# USB.net
KiCad netlist of a schematic drawn in Altium Designer
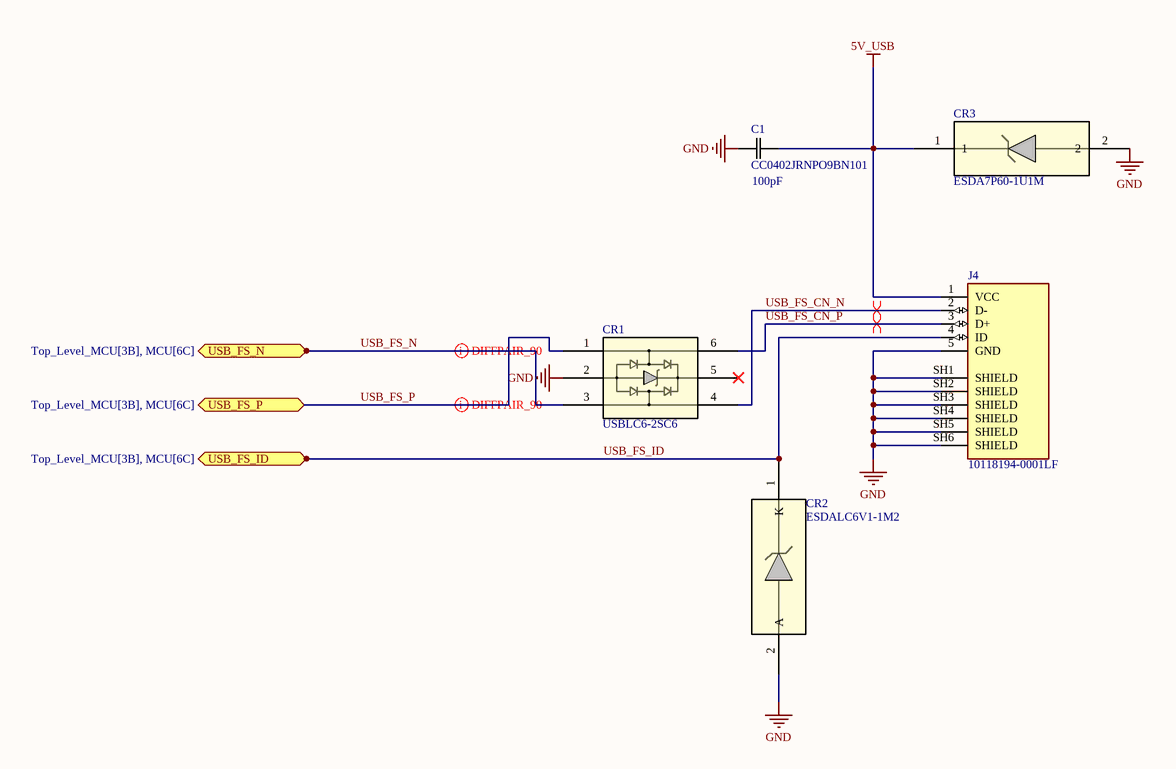
[diagram p0: USB.SchDoc]

(export (version "E")
  (design (tool "Eeschema 10.0.6"))
  (components
    (comp (ref "C1")
      (value "CC0402JRNPO9BN101")
      (footprint "CAP_CC0402_YAG")
      (description "CAPACITOR; SMT (0402); CERAMIC CHIP; 100PF; 50V; TOL=5%; TG=-55 DEGC TO +125 DEGC; TC=C0G")
      (fields (field (name "COPYRIGHT") "Copyright (C) 2025 Ultra Librarian. All rights reserved."))
      (libsource (lib "CC0402JRNPO9BN101") (part "CC0402JRNPO9BN101"))
    )
    (comp (ref "CR1")
      (value "USBLC6-2SC6")
      (footprint "SOT23-6L_STM")
      (description "ESD Protection for USB 2.0 High Speed")
      (fields (field (name "COPYRIGHT") "Copyright (C) 2025 Ultra Librarian. All rights reserved."))
      (libsource (lib "USBLC6-2SC6") (part "USBLC6-2SC6"))
    )
    (comp (ref "CR2")
      (value "ESDALC6V1-1M2")
      (footprint "SOD882_STM")
      (fields (field (name "COPYRIGHT") "Copyright (C) 2025 Ultra Librarian. All rights reserved."))
      (libsource (lib "ESDALC6V1-1M2") (part "ESDALC6V1-1M2"))
    )
    (comp (ref "CR3")
      (value "ESDA7P60-1U1M")
      (footprint "ZDO_1610_STM")
      (description "60 A - 8/20 us, 5 V TVS in QFN-2L")
      (fields (field (name "COPYRIGHT") "Copyright (C) 2025 Ultra Librarian. All rights reserved."))
      (libsource (lib "ESDA7P60-1U1M") (part "ESDA7P60-1U1M"))
    )
    (comp (ref "J4")
      (value "10118194-0001LF")
      (footprint "AMPHENOL_10118194-0001LF")
      (description "Micro USB, Input Output Connectors, B TYPE RECEPTACLE with flange")
      (fields (field (name "MF") "Amphenol ICC"))
      (libsource (lib "10118194-0001LF") (part "10118194-0001LF"))
    )
  )
  (nets
    (net (code "1") (name "/USB_FS_CN_N") (class "Default")
      (node (ref "CR1") (pin "4") (pinfunction "4_4") (pintype "passive"))
      (node (ref "J4") (pin "2") (pinfunction "D-_2") (pintype "bidirectional"))
    )
    (net (code "2") (name "/USB_FS_CN_P") (class "Default")
      (node (ref "CR1") (pin "6") (pinfunction "6_6") (pintype "passive"))
      (node (ref "J4") (pin "3") (pinfunction "D+_3") (pintype "bidirectional"))
    )
    (net (code "3") (name "/USB_FS_ID") (class "Default")
      (node (ref "CR2") (pin "1") (pinfunction "K_1") (pintype "passive"))
      (node (ref "J4") (pin "4") (pinfunction "ID_4") (pintype "bidirectional"))
    )
    (net (code "4") (name "/USB_FS_N") (class "Default")
      (node (ref "CR1") (pin "3") (pinfunction "3_3") (pintype "passive"))
    )
    (net (code "5") (name "/USB_FS_P") (class "Default")
      (node (ref "CR1") (pin "1") (pinfunction "1_1") (pintype "passive"))
    )
    (net (code "6") (name "5V_USB") (class "Default")
      (node (ref "C1") (pin "2") (pinfunction "2_2") (pintype "passive"))
      (node (ref "CR3") (pin "1") (pinfunction "1_1") (pintype "passive"))
      (node (ref "J4") (pin "1") (pinfunction "VCC_1") (pintype "power_in"))
    )
    (net (code "7") (name "GND") (class "Default")
      (node (ref "C1") (pin "1") (pinfunction "1_1") (pintype "passive"))
      (node (ref "CR1") (pin "2") (pinfunction "2_2") (pintype "passive"))
      (node (ref "CR2") (pin "2") (pinfunction "A_2") (pintype "passive"))
      (node (ref "CR3") (pin "2") (pinfunction "2_2") (pintype "passive"))
      (node (ref "J4") (pin "5") (pinfunction "GND_5") (pintype "power_in"))
      (node (ref "J4") (pin "SH1") (pinfunction "SHIELD_SH1") (pintype "passive"))
      (node (ref "J4") (pin "SH2") (pinfunction "SHIELD_SH2") (pintype "passive"))
      (node (ref "J4") (pin "SH3") (pinfunction "SHIELD_SH3") (pintype "passive"))
      (node (ref "J4") (pin "SH4") (pinfunction "SHIELD_SH4") (pintype "passive"))
      (node (ref "J4") (pin "SH5") (pinfunction "SHIELD_SH5") (pintype "passive"))
      (node (ref "J4") (pin "SH6") (pinfunction "SHIELD_SH6") (pintype "passive"))
    )
    (net (code "8") (name "unconnected-(CR1-Pad5)") (class "Default")
      (node (ref "CR1") (pin "5") (pinfunction "5_5") (pintype "passive+no_connect"))
    )
  )
)
